# hbridge.net
KiCad netlist of a schematic drawn in EAGLE
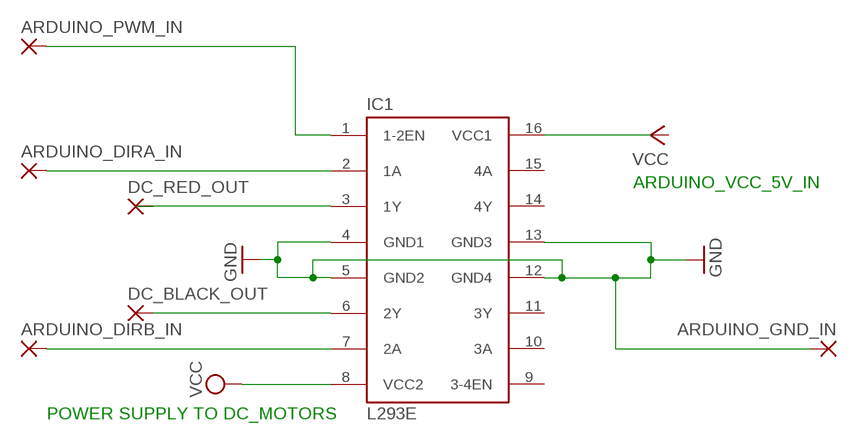
[diagram p0: schematic, sheet 1]

(export (version "E")
  (design (tool "Eeschema 10.0.6"))
  (components
    (comp (ref "ARDUINO_DIRA_IN")
      (value "SMD2")
      (footprint "eagle-import:SMD1,27-2,54")
      (libsource (lib "eagle-import") (part "SMD2"))
    )
    (comp (ref "ARDUINO_DIRB_IN")
      (value "SMD2")
      (footprint "eagle-import:SMD1,27-2,54")
      (libsource (lib "eagle-import") (part "SMD2"))
    )
    (comp (ref "ARDUINO_GND_IN")
      (value "SMD2")
      (footprint "eagle-import:SMD1,27-2,54")
      (libsource (lib "eagle-import") (part "SMD2"))
    )
    (comp (ref "ARDUINO_PWM_IN")
      (value "SMD2")
      (footprint "eagle-import:SMD1,27-2,54")
      (libsource (lib "eagle-import") (part "SMD2"))
    )
    (comp (ref "DC_BLACK_OUT")
      (value "SMD2")
      (footprint "eagle-import:SMD1,27-2,54")
      (libsource (lib "eagle-import") (part "SMD2"))
    )
    (comp (ref "DC_RED_OUT")
      (value "SMD2")
      (footprint "eagle-import:SMD1,27-2,54")
      (libsource (lib "eagle-import") (part "SMD2"))
    )
    (comp (ref "IC1")
      (value "L293E")
      (footprint "eagle-import:DIL16")
      (fields (field (name "MF") "Arrow Electronics"))
      (libsource (lib "eagle-import") (part "L293E"))
    )
  )
  (nets
    (net (code "1") (name "GND") (class "Default")
      (node (ref "ARDUINO_GND_IN") (pin "1") (pinfunction "P_1") (pintype "passive"))
      (node (ref "IC1") (pin "12") (pinfunction "GND4_12") (pintype "power_in"))
      (node (ref "IC1") (pin "13") (pinfunction "GND3_13") (pintype "power_in"))
      (node (ref "IC1") (pin "4") (pinfunction "GND1_4") (pintype "power_in"))
      (node (ref "IC1") (pin "5") (pinfunction "GND2_5") (pintype "power_in"))
    )
    (net (code "2") (name "Net-(ARDUINO_DIRA_IN-P)") (class "Default")
      (node (ref "ARDUINO_DIRA_IN") (pin "1") (pinfunction "P_1") (pintype "passive"))
      (node (ref "IC1") (pin "2") (pinfunction "1A_2") (pintype "input"))
    )
    (net (code "3") (name "Net-(ARDUINO_DIRB_IN-P)") (class "Default")
      (node (ref "ARDUINO_DIRB_IN") (pin "1") (pinfunction "P_1") (pintype "passive"))
      (node (ref "IC1") (pin "7") (pinfunction "2A_7") (pintype "input"))
    )
    (net (code "4") (name "Net-(ARDUINO_PWM_IN-P)") (class "Default")
      (node (ref "ARDUINO_PWM_IN") (pin "1") (pinfunction "P_1") (pintype "passive"))
      (node (ref "IC1") (pin "1") (pinfunction "1-2EN_1") (pintype "input"))
    )
    (net (code "5") (name "Net-(DC_BLACK_OUT-P)") (class "Default")
      (node (ref "DC_BLACK_OUT") (pin "1") (pinfunction "P_1") (pintype "passive"))
      (node (ref "IC1") (pin "6") (pinfunction "2Y_6") (pintype "output"))
    )
    (net (code "6") (name "Net-(DC_RED_OUT-P)") (class "Default")
      (node (ref "DC_RED_OUT") (pin "1") (pinfunction "P_1") (pintype "passive"))
      (node (ref "IC1") (pin "3") (pinfunction "1Y_3") (pintype "output"))
    )
    (net (code "7") (name "VCC") (class "Default")
      (node (ref "IC1") (pin "8") (pinfunction "VCC2_8") (pintype "power_in"))
    )
    (net (code "8") (name "unconnected-(IC1-3-4EN-Pad9)") (class "Default")
      (node (ref "IC1") (pin "9") (pinfunction "3-4EN_9") (pintype "input"))
    )
    (net (code "9") (name "unconnected-(IC1-3A-Pad10)") (class "Default")
      (node (ref "IC1") (pin "10") (pinfunction "3A_10") (pintype "input"))
    )
    (net (code "10") (name "unconnected-(IC1-3Y-Pad11)") (class "Default")
      (node (ref "IC1") (pin "11") (pinfunction "3Y_11") (pintype "output"))
    )
    (net (code "11") (name "unconnected-(IC1-4A-Pad15)") (class "Default")
      (node (ref "IC1") (pin "15") (pinfunction "4A_15") (pintype "input"))
    )
    (net (code "12") (name "unconnected-(IC1-4Y-Pad14)") (class "Default")
      (node (ref "IC1") (pin "14") (pinfunction "4Y_14") (pintype "output"))
    )
    (net (code "13") (name "unconnected-(IC1-VCC1-Pad16)") (class "Default")
      (node (ref "IC1") (pin "16") (pinfunction "VCC1_16") (pintype "power_in"))
    )
  )
)
